# 02-ZYNQ_BANK_0.net
KiCad netlist of a schematic drawn in Altium Designer
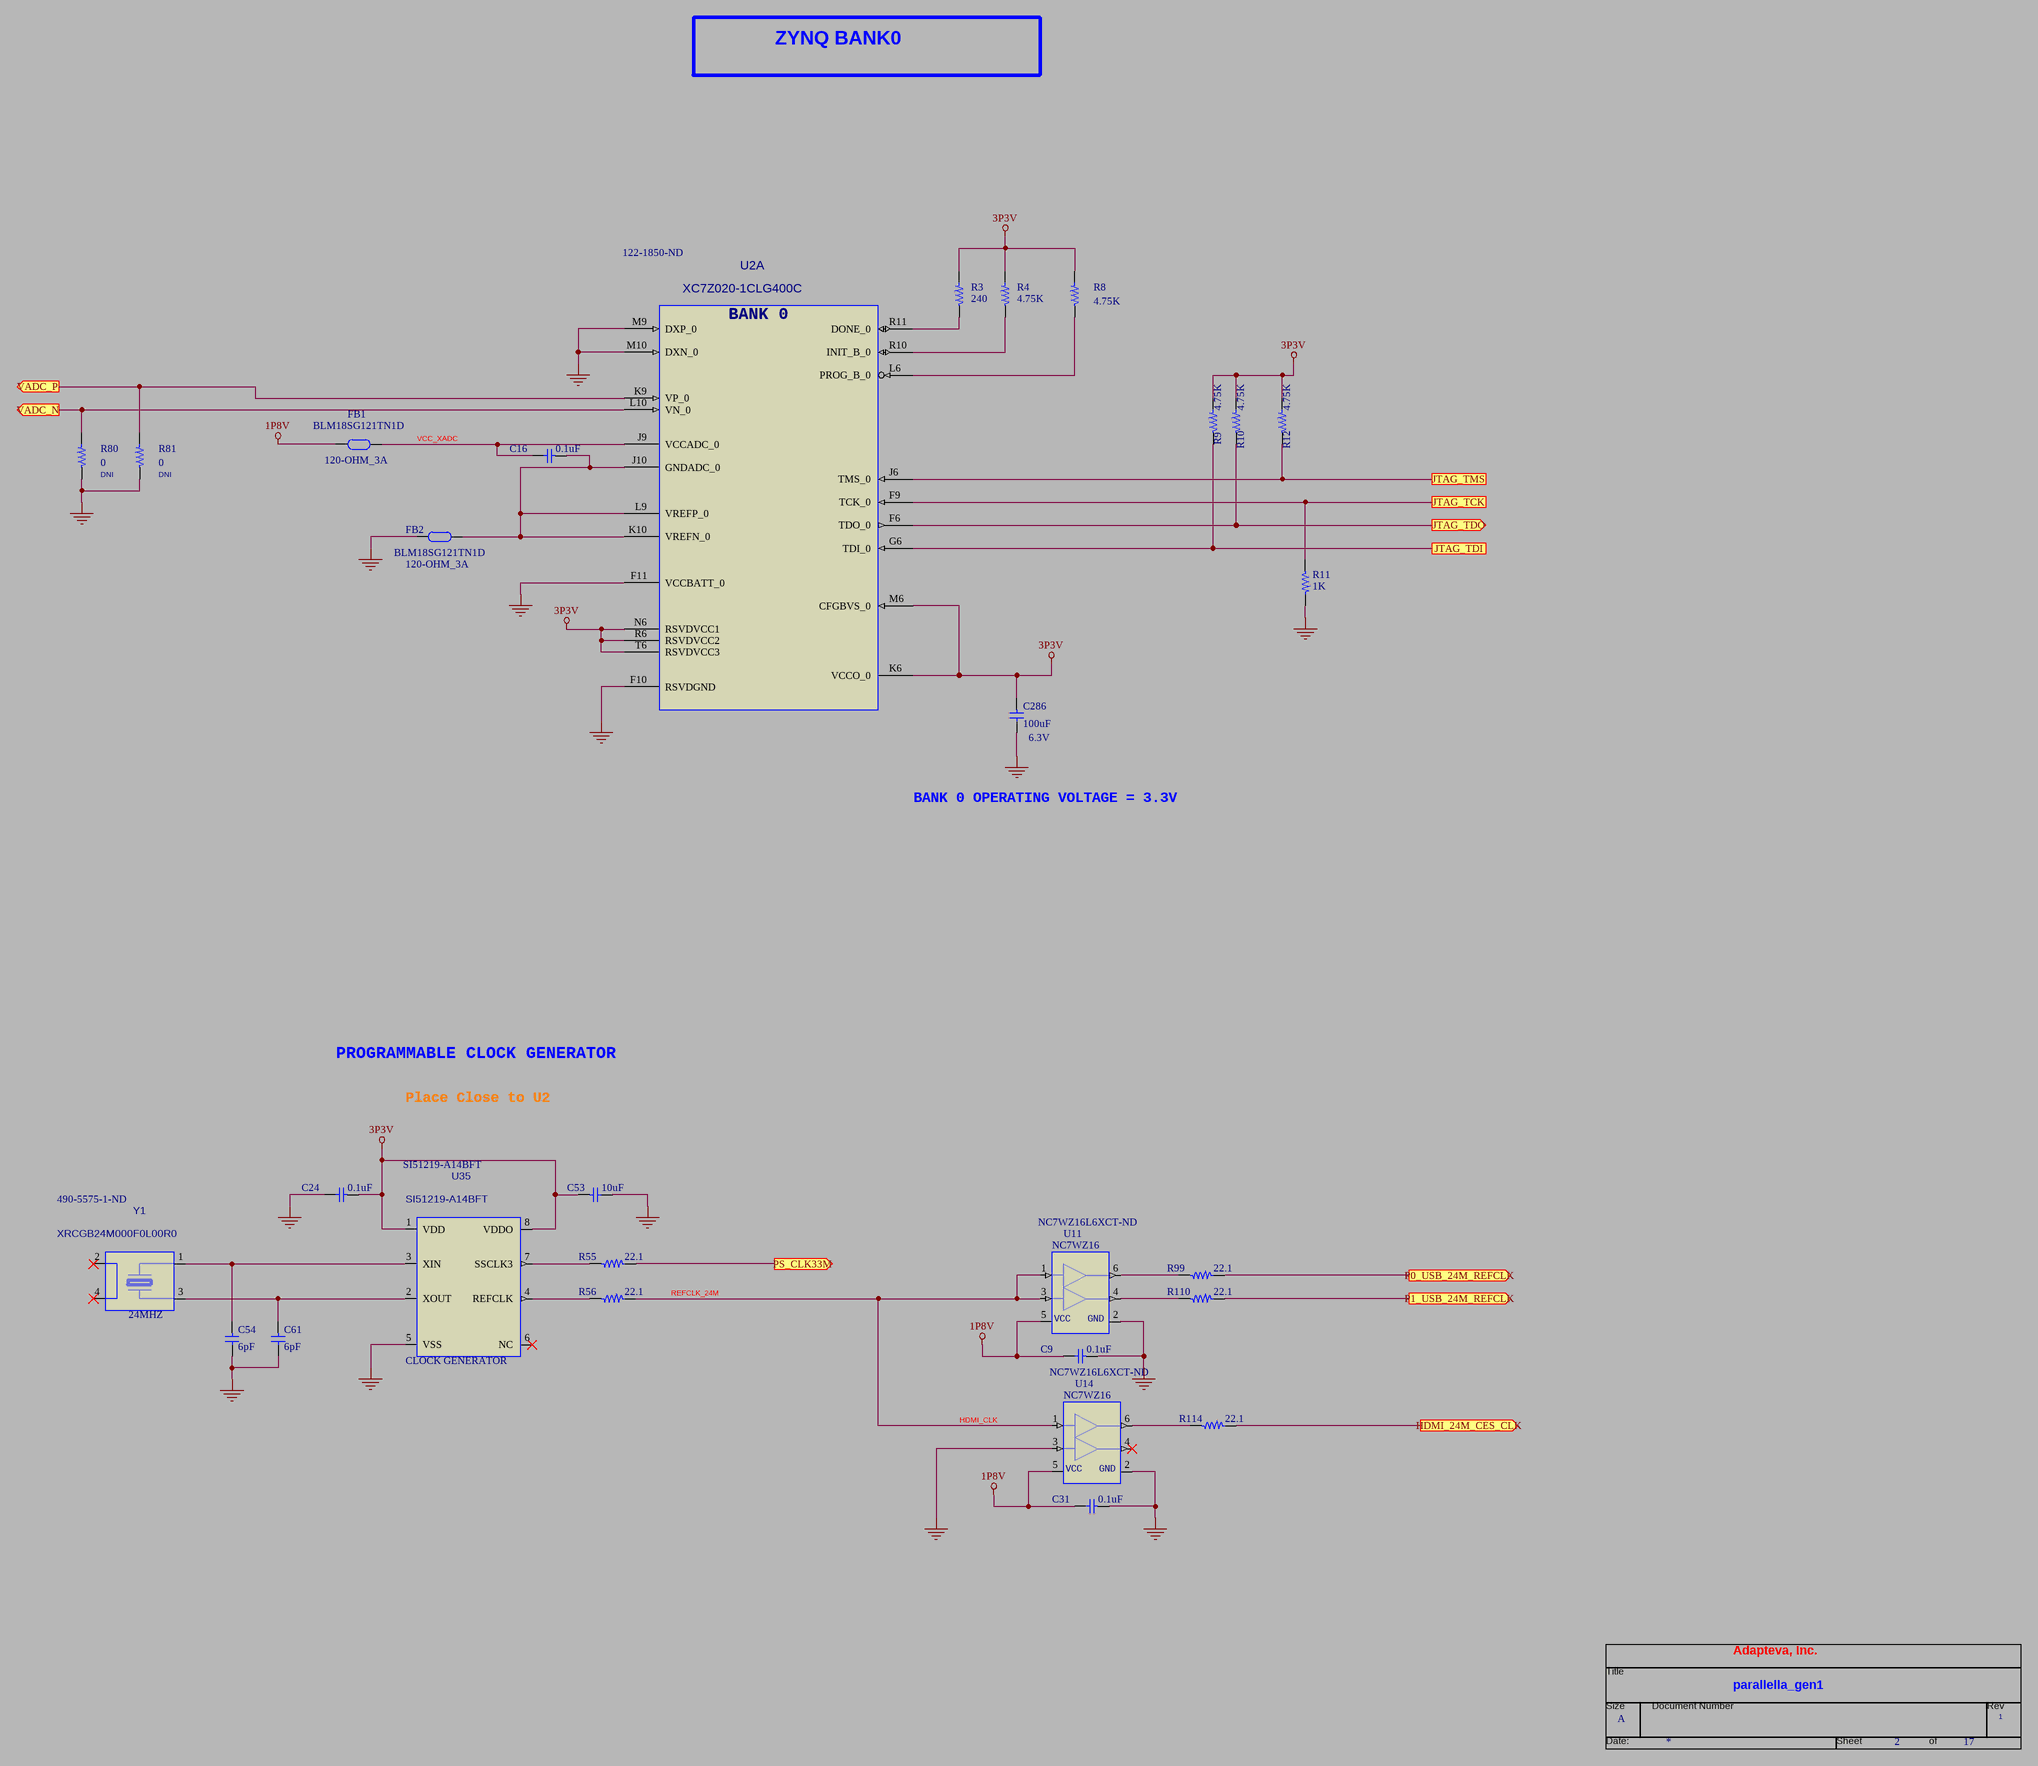
[diagram p0: 02-ZYNQ BANK 0.SchDoc]

(export (version "E")
  (design (tool "Eeschema 10.0.6"))
  (components
    (comp (ref "C9")
      (value "0.1uF")
      (footprint "C0402")
      (description "CAP, 0402, 0.1UF, X5R, 35V")
      (fields (field (name "MFG PART NO") "GMK105BJ104KV-F") (field (name "MFG") "TAIYO YUDEN"))
      (libsource (lib "*") (part "CAP0402_0P1UF_X5R_35V"))
    )
    (comp (ref "C16")
      (value "0.1uF")
      (footprint "C0402")
      (description "CAP, 0402, 0.1UF, X5R, 35V")
      (fields (field (name "MFG PART NO") "GMK105BJ104KV-F") (field (name "MFG") "TAIYO YUDEN"))
      (libsource (lib "*") (part "CAP0402_0P1UF_X5R_35V"))
    )
    (comp (ref "C24")
      (value "0.1uF")
      (footprint "C0402")
      (description "CAP, 0402, 0.1UF, X5R, 35V")
      (fields (field (name "MFG PART NO") "GMK105BJ104KV-F") (field (name "MFG") "TAIYO YUDEN"))
      (libsource (lib "*") (part "CAP0402_0P1UF_X5R_35V"))
    )
    (comp (ref "C31")
      (value "0.1uF")
      (footprint "C0402")
      (description "CAP, 0402, 0.1UF, X5R, 35V")
      (fields (field (name "MFG PART NO") "GMK105BJ104KV-F") (field (name "MFG") "TAIYO YUDEN"))
      (libsource (lib "*") (part "CAP0402_0P1UF_X5R_35V"))
    )
    (comp (ref "C53")
      (value "10uF")
      (footprint "C0603")
      (description "CAP, 0603, 10UF, X5R, 10V")
      (fields (field (name "MFG") "TAIYO YUDEN") (field (name "MFG PART NO") "LMK107BJ106MALTD"))
      (libsource (lib "*") (part "CAP0603_10UF_X5R"))
    )
    (comp (ref "C54")
      (value "6pF")
      (footprint "C0402")
      (description "CAP, 0402, 6PF, NPO, 50V")
      (fields (field (name "MFG PART NO") "C1005COG1H060D050BA") (field (name "MFG") "TDK"))
      (libsource (lib "*") (part "CAP0402_6PF_NPO_50V"))
    )
    (comp (ref "C61")
      (value "6pF")
      (footprint "C0402")
      (description "CAP, 0402, 6PF, NPO, 50V")
      (fields (field (name "MFG PART NO") "C1005COG1H060D050BA") (field (name "MFG") "TDK"))
      (libsource (lib "*") (part "CAP0402_6PF_NPO_50V"))
    )
    (comp (ref "C286")
      (value "100uF")
      (footprint "C1210")
      (description "CAP, 1210, 100UF, X5R, 6.3V, LOW ESR")
      (fields
        (field (name "VOLTAGE") "6.3V")
        (field (name "MFG PART NO") "GRM32ER60J107ME20L")
        (field (name "MFG") "MURATA")
      )
      (libsource (lib "*") (part "CAP1210_100UF_X5R_LOESR"))
    )
    (comp (ref "FB1")
      (value "120-OHM_3A")
      (footprint "BEAD_0603")
      (description "FERRITE, BEAD, FILTER, 0603, 3A")
      (fields (field (name "VENDOR PN") "BLM18SG121TN1D"))
      (libsource (lib "*") (part "BLM18SG121TN1D"))
    )
    (comp (ref "FB2")
      (value "120-OHM_3A")
      (footprint "BEAD_0603")
      (description "FERRITE, BEAD, FILTER, 0603, 3A")
      (fields (field (name "VENDOR PN") "BLM18SG121TN1D"))
      (libsource (lib "*") (part "BLM18SG121TN1D"))
    )
    (comp (ref "R3")
      (value "240")
      (footprint "R0402")
      (description "RES, 0402, 240, 1%")
      (fields (field (name "MFG") "VISHAY") (field (name "MFG PART NO") "CRCW0402240RFKED"))
      (libsource (lib "*") (part "RES0402_240"))
    )
    (comp (ref "R4")
      (value "4.75K")
      (footprint "R0402")
      (description "RES, 0402, 4.75K, 1%")
      (fields (field (name "MFG") "VISHAY") (field (name "MFG PART NO") "CRCW04024K75FKED"))
      (libsource (lib "*") (part "RES0402_4K75"))
    )
    (comp (ref "R8")
      (value "4.75K")
      (footprint "R0402")
      (description "RES, 0402, 4.75K, 1%")
      (fields (field (name "MFG") "VISHAY") (field (name "MFG PART NO") "CRCW04024K75FKED"))
      (libsource (lib "*") (part "RES0402_4K75"))
    )
    (comp (ref "R9")
      (value "4.75K")
      (footprint "R0402")
      (description "RES, 0402, 4.75K, 1%")
      (fields (field (name "MFG") "VISHAY") (field (name "MFG PART NO") "CRCW04024K75FKED"))
      (libsource (lib "*") (part "RES0402_4K75"))
    )
    (comp (ref "R10")
      (value "4.75K")
      (footprint "R0402")
      (description "RES, 0402, 4.75K, 1%")
      (fields (field (name "MFG") "VISHAY") (field (name "MFG PART NO") "CRCW04024K75FKED"))
      (libsource (lib "*") (part "RES0402_4K75"))
    )
    (comp (ref "R11")
      (value "1K")
      (footprint "R0402")
      (description "RES, 0402, 1K")
      (fields (field (name "MFG") "VISHAY") (field (name "MFG PART NO") "CRCW04021K00FKED"))
      (libsource (lib "*") (part "RES0402_1K"))
    )
    (comp (ref "R12")
      (value "4.75K")
      (footprint "R0402")
      (description "RES, 0402, 4.75K, 1%")
      (fields (field (name "MFG") "VISHAY") (field (name "MFG PART NO") "CRCW04024K75FKED"))
      (libsource (lib "*") (part "RES0402_4K75"))
    )
    (comp (ref "R55")
      (value "22.1")
      (footprint "R0402")
      (description "RES, 0402, 22.1, 1%")
      (fields (field (name "MFG") "VISHAY") (field (name "MFG PART NO") "CRCW040222R1FKED"))
      (libsource (lib "*") (part "RES0402_22R1"))
    )
    (comp (ref "R56")
      (value "22.1")
      (footprint "R0402")
      (description "RES, 0402, 22.1, 1%")
      (fields (field (name "MFG") "VISHAY") (field (name "MFG PART NO") "CRCW040222R1FKED"))
      (libsource (lib "*") (part "RES0402_22R1"))
    )
    (comp (ref "R80")
      (value "0")
      (footprint "R0402")
      (description "RES, 0402, 0 OHM, 1%")
      (fields
        (field (name "MFG") "VISHAY")
        (field (name "MFG PART NO") "CRCW04020000Z0ED")
        (field (name "INSTALL") "DNI")
      )
      (libsource (lib "*") (part "RES0402_0"))
    )
    (comp (ref "R81")
      (value "0")
      (footprint "R0402")
      (description "RES, 0402, 0 OHM, 1%")
      (fields
        (field (name "MFG") "VISHAY")
        (field (name "MFG PART NO") "CRCW04020000Z0ED")
        (field (name "INSTALL") "DNI")
      )
      (libsource (lib "*") (part "RES0402_0"))
    )
    (comp (ref "R99")
      (value "22.1")
      (footprint "R0402")
      (description "RES, 0402, 22.1, 1%")
      (fields (field (name "MFG") "VISHAY") (field (name "MFG PART NO") "CRCW040222R1FKED"))
      (libsource (lib "*") (part "RES0402_22R1"))
    )
    (comp (ref "R110")
      (value "22.1")
      (footprint "R0402")
      (description "RES, 0402, 22.1, 1%")
      (fields (field (name "MFG") "VISHAY") (field (name "MFG PART NO") "CRCW040222R1FKED"))
      (libsource (lib "*") (part "RES0402_22R1"))
    )
    (comp (ref "R114")
      (value "22.1")
      (footprint "R0402")
      (description "RES, 0402, 22.1, 1%")
      (fields (field (name "MFG") "VISHAY") (field (name "MFG PART NO") "CRCW040222R1FKED"))
      (libsource (lib "*") (part "RES0402_22R1"))
    )
    (comp (ref "U2")
      (value "7Z020-CLG400")
      (footprint "CBGA400_17SQ_1P6H_P8MMP")
      (description "IC, EPP, XILINX, ZYNQ, 7Z020, CLG400")
      (fields
        (field (name "VENDOR PN") "XC7Z020-1CLG400C")
        (field (name "SUPPLIER PART NUMBER 1") "122-1850-ND")
      )
      (libsource (lib "*") (part "ZYNQ_7Z020_CLG400"))
    )
    (comp (ref "U11")
      (value "NC7WZ16")
      (footprint "SC_70_6PSMT")
      (fields
        (field (name "MFG PART NO") "NC7WZ16P6X")
        (field (name "MFG") "FAIRCHILD")
        (field (name "SUPPLIER PART NUMBER 1") "NC7WZ16L6XCT-ND")
      )
      (libsource (lib "*") (part "NC7WZ16"))
    )
    (comp (ref "U14")
      (value "NC7WZ16")
      (footprint "SC_70_6PSMT")
      (fields
        (field (name "MFG PART NO") "NC7WZ16P6X")
        (field (name "MFG") "FAIRCHILD")
        (field (name "SUPPLIER PART NUMBER 1") "NC7WZ16L6XCT-ND")
      )
      (libsource (lib "*") (part "NC7WZ16"))
    )
    (comp (ref "U35")
      (value "CLOCK GENERATOR")
      (footprint "TSSOP8_3X4P4X1P2H_P65MMP")
      (description "IC, PROGRAMMABLE CLOCK GEN, 3 OUTPUTS, TSSOP8")
      (fields
        (field (name "MFG") "SILICON LABS")
        (field (name "MFG PART NO") "SI51219-A14BFT")
        (field (name "SUPPLIER PART NUMBER 1") "SI51219-A14BFT")
      )
      (libsource (lib "*") (part "IC_SI51219"))
    )
    (comp (ref "Y1")
      (value "24MHZ")
      (footprint "OSC4_1P6X2X7MMH")
      (description "XTAL, 2X1.6MM, 24MHZ, 4PIN, SMT")
      (fields
        (field (name "VENDOR PN") "XRCGB24M000F0L00R0")
        (field (name "SUPPLIER PART NUMBER 1") "490-5575-1-ND")
      )
      (libsource (lib "*") (part "CRYSTAL_4P_24MHZ"))
    )
  )
  (nets
    (net (code "1") (name "/HDMI_24M_CES_CLK") (class "Default")
      (node (ref "R114") (pin "2") (pinfunction "2_2") (pintype "passive"))
    )
    (net (code "2") (name "/HDMI_CLK") (class "Default")
      (node (ref "R56") (pin "2") (pinfunction "2_2") (pintype "passive"))
      (node (ref "U11") (pin "1") (pinfunction "A1_1") (pintype "input"))
      (node (ref "U11") (pin "3") (pinfunction "A2_3") (pintype "input"))
      (node (ref "U14") (pin "1") (pinfunction "A1_1") (pintype "input"))
    )
    (net (code "3") (name "/JTAG_TCK") (class "Default")
      (node (ref "R11") (pin "1") (pinfunction "1_1") (pintype "passive"))
      (node (ref "U2") (pin "F9") (pinfunction "TCK_0_F9") (pintype "input"))
    )
    (net (code "4") (name "/JTAG_TDI") (class "Default")
      (node (ref "R9") (pin "1") (pinfunction "1_1") (pintype "passive"))
      (node (ref "U2") (pin "G6") (pinfunction "TDI_0_G6") (pintype "input"))
    )
    (net (code "5") (name "/JTAG_TDO") (class "Default")
      (node (ref "R10") (pin "1") (pinfunction "1_1") (pintype "passive"))
      (node (ref "U2") (pin "F6") (pinfunction "TDO_0_F6") (pintype "output"))
    )
    (net (code "6") (name "/JTAG_TMS") (class "Default")
      (node (ref "R12") (pin "1") (pinfunction "1_1") (pintype "passive"))
      (node (ref "U2") (pin "J6") (pinfunction "TMS_0_J6") (pintype "input"))
    )
    (net (code "7") (name "/P0_USB_24M_REFCLK") (class "Default")
      (node (ref "R99") (pin "2") (pinfunction "2_2") (pintype "passive"))
    )
    (net (code "8") (name "/P1_USB_24M_REFCLK") (class "Default")
      (node (ref "R110") (pin "2") (pinfunction "2_2") (pintype "passive"))
    )
    (net (code "9") (name "/PS_CLK33M") (class "Default")
      (node (ref "R55") (pin "2") (pinfunction "2_2") (pintype "passive"))
    )
    (net (code "10") (name "/VADC_N") (class "Default")
      (node (ref "R80") (pin "2") (pinfunction "2_2") (pintype "passive"))
      (node (ref "U2") (pin "L10") (pinfunction "VN_0_L10") (pintype "input"))
    )
    (net (code "11") (name "/VADC_P") (class "Default")
      (node (ref "R81") (pin "2") (pinfunction "2_2") (pintype "passive"))
      (node (ref "U2") (pin "K9") (pinfunction "VP_0_K9") (pintype "input"))
    )
    (net (code "12") (name "/VCC_XADC") (class "Default")
      (node (ref "C16") (pin "2") (pinfunction "2_2") (pintype "passive"))
      (node (ref "FB1") (pin "2") (pinfunction "2_2") (pintype "passive"))
      (node (ref "U2") (pin "J9") (pinfunction "VCCADC_0_J9") (pintype "power_in"))
    )
    (net (code "13") (name "1P8V") (class "Default")
      (node (ref "C31") (pin "2") (pinfunction "2_2") (pintype "passive"))
      (node (ref "C9") (pin "2") (pinfunction "2_2") (pintype "passive"))
      (node (ref "FB1") (pin "1") (pinfunction "1_1") (pintype "passive"))
      (node (ref "U11") (pin "5") (pinfunction "VCC_5") (pintype "power_in"))
      (node (ref "U14") (pin "5") (pinfunction "VCC_5") (pintype "power_in"))
    )
    (net (code "14") (name "3P3V") (class "Default")
      (node (ref "C24") (pin "1") (pinfunction "1_1") (pintype "passive"))
      (node (ref "C286") (pin "1") (pinfunction "1_1") (pintype "passive"))
      (node (ref "C53") (pin "1") (pinfunction "1_1") (pintype "passive"))
      (node (ref "R10") (pin "2") (pinfunction "2_2") (pintype "passive"))
      (node (ref "R12") (pin "2") (pinfunction "2_2") (pintype "passive"))
      (node (ref "R3") (pin "2") (pinfunction "2_2") (pintype "passive"))
      (node (ref "R4") (pin "2") (pinfunction "2_2") (pintype "passive"))
      (node (ref "R8") (pin "2") (pinfunction "2_2") (pintype "passive"))
      (node (ref "R9") (pin "2") (pinfunction "2_2") (pintype "passive"))
      (node (ref "U2") (pin "K6") (pinfunction "VCCO_0_K6") (pintype "power_in"))
      (node (ref "U2") (pin "M6") (pinfunction "CFGBVS_0_M6") (pintype "input"))
      (node (ref "U2") (pin "N6") (pinfunction "RSVDVCC1_N6") (pintype "passive"))
      (node (ref "U2") (pin "R6") (pinfunction "RSVDVCC2_R6") (pintype "passive"))
      (node (ref "U2") (pin "T6") (pinfunction "RSVDVCC3_T6") (pintype "passive"))
      (node (ref "U35") (pin "1") (pinfunction "VDD_1") (pintype "power_in"))
      (node (ref "U35") (pin "8") (pinfunction "VDDO_8") (pintype "power_in"))
    )
    (net (code "15") (name "GND") (class "Default")
      (node (ref "C24") (pin "2") (pinfunction "2_2") (pintype "passive"))
      (node (ref "C286") (pin "2") (pinfunction "2_2") (pintype "passive"))
      (node (ref "C31") (pin "1") (pinfunction "1_1") (pintype "passive"))
      (node (ref "C53") (pin "2") (pinfunction "2_2") (pintype "passive"))
      (node (ref "C54") (pin "2") (pinfunction "2_2") (pintype "passive"))
      (node (ref "C61") (pin "2") (pinfunction "2_2") (pintype "passive"))
      (node (ref "C9") (pin "1") (pinfunction "1_1") (pintype "passive"))
      (node (ref "FB2") (pin "1") (pinfunction "1_1") (pintype "passive"))
      (node (ref "R11") (pin "2") (pinfunction "2_2") (pintype "passive"))
      (node (ref "R80") (pin "1") (pinfunction "1_1") (pintype "passive"))
      (node (ref "R81") (pin "1") (pinfunction "1_1") (pintype "passive"))
      (node (ref "U11") (pin "2") (pinfunction "GND_2") (pintype "power_in"))
      (node (ref "U14") (pin "2") (pinfunction "GND_2") (pintype "power_in"))
      (node (ref "U14") (pin "3") (pinfunction "A2_3") (pintype "input"))
      (node (ref "U2") (pin "F10") (pinfunction "RSVDGND_F10") (pintype "power_in"))
      (node (ref "U2") (pin "F11") (pinfunction "VCCBATT_0_F11") (pintype "power_in"))
      (node (ref "U2") (pin "M10") (pinfunction "DXN_0_M10") (pintype "input"))
      (node (ref "U2") (pin "M9") (pinfunction "DXP_0_M9") (pintype "input"))
      (node (ref "U35") (pin "5") (pinfunction "VSS_5") (pintype "power_in"))
    )
    (net (code "16") (name "Net-(U2A-DONE_0)") (class "Default")
      (node (ref "R3") (pin "1") (pinfunction "1_1") (pintype "passive"))
      (node (ref "U2") (pin "R11") (pinfunction "DONE_0_R11") (pintype "bidirectional"))
    )
    (net (code "17") (name "Net-(U2A-GNDADC_0)") (class "Default")
      (node (ref "C16") (pin "1") (pinfunction "1_1") (pintype "passive"))
      (node (ref "FB2") (pin "2") (pinfunction "2_2") (pintype "passive"))
      (node (ref "U2") (pin "J10") (pinfunction "GNDADC_0_J10") (pintype "power_in"))
      (node (ref "U2") (pin "K10") (pinfunction "VREFN_0_K10") (pintype "power_in"))
      (node (ref "U2") (pin "L9") (pinfunction "VREFP_0_L9") (pintype "power_in"))
    )
    (net (code "18") (name "Net-(U2A-INIT_B_0)") (class "Default")
      (node (ref "R4") (pin "1") (pinfunction "1_1") (pintype "passive"))
      (node (ref "U2") (pin "R10") (pinfunction "INIT_B_0_R10") (pintype "bidirectional"))
    )
    (net (code "19") (name "Net-(U2A-PROG_B_0)") (class "Default")
      (node (ref "R8") (pin "1") (pinfunction "1_1") (pintype "passive"))
      (node (ref "U2") (pin "L6") (pinfunction "PROG_B_0_L6") (pintype "input"))
    )
    (net (code "20") (name "Net-(U11-Y1)") (class "Default")
      (node (ref "R99") (pin "1") (pinfunction "1_1") (pintype "passive"))
      (node (ref "U11") (pin "6") (pinfunction "Y1_6") (pintype "output"))
    )
    (net (code "21") (name "Net-(U11-Y2)") (class "Default")
      (node (ref "R110") (pin "1") (pinfunction "1_1") (pintype "passive"))
      (node (ref "U11") (pin "4") (pinfunction "Y2_4") (pintype "output"))
    )
    (net (code "22") (name "Net-(U14-Y1)") (class "Default")
      (node (ref "R114") (pin "1") (pinfunction "1_1") (pintype "passive"))
      (node (ref "U14") (pin "6") (pinfunction "Y1_6") (pintype "output"))
    )
    (net (code "23") (name "Net-(U35-REFCLK)") (class "Default")
      (node (ref "R56") (pin "1") (pinfunction "1_1") (pintype "passive"))
      (node (ref "U35") (pin "4") (pinfunction "REFCLK_4") (pintype "output"))
    )
    (net (code "24") (name "Net-(U35-SSCLK3)") (class "Default")
      (node (ref "R55") (pin "1") (pinfunction "1_1") (pintype "passive"))
      (node (ref "U35") (pin "7") (pinfunction "SSCLK3_7") (pintype "output"))
    )
    (net (code "25") (name "Net-(U35-XIN)") (class "Default")
      (node (ref "C54") (pin "1") (pinfunction "1_1") (pintype "passive"))
      (node (ref "U35") (pin "3") (pinfunction "XIN_3") (pintype "bidirectional"))
      (node (ref "Y1") (pin "1") (pinfunction "1_1") (pintype "passive"))
    )
    (net (code "26") (name "Net-(U35-XOUT)") (class "Default")
      (node (ref "C61") (pin "1") (pinfunction "1_1") (pintype "passive"))
      (node (ref "U35") (pin "2") (pinfunction "XOUT_2") (pintype "bidirectional"))
      (node (ref "Y1") (pin "3") (pinfunction "3_3") (pintype "passive"))
    )
    (net (code "27") (name "unconnected-(U14-Y2-Pad4)") (class "Default")
      (node (ref "U14") (pin "4") (pinfunction "Y2_4") (pintype "output+no_connect"))
    )
    (net (code "28") (name "unconnected-(U35-NC-Pad6)") (class "Default")
      (node (ref "U35") (pin "6") (pinfunction "NC_6") (pintype "passive+no_connect"))
    )
    (net (code "29") (name "unconnected-(Y1-Pad2)") (class "Default")
      (node (ref "Y1") (pin "2") (pinfunction "2_2") (pintype "passive+no_connect"))
    )
    (net (code "30") (name "unconnected-(Y1-Pad4)") (class "Default")
      (node (ref "Y1") (pin "4") (pinfunction "4_4") (pintype "passive+no_connect"))
    )
  )
)
